# ProDocument_Schematic1_1_2023-10-08.net
KiCad netlist of a schematic drawn in EasyEDA Pro
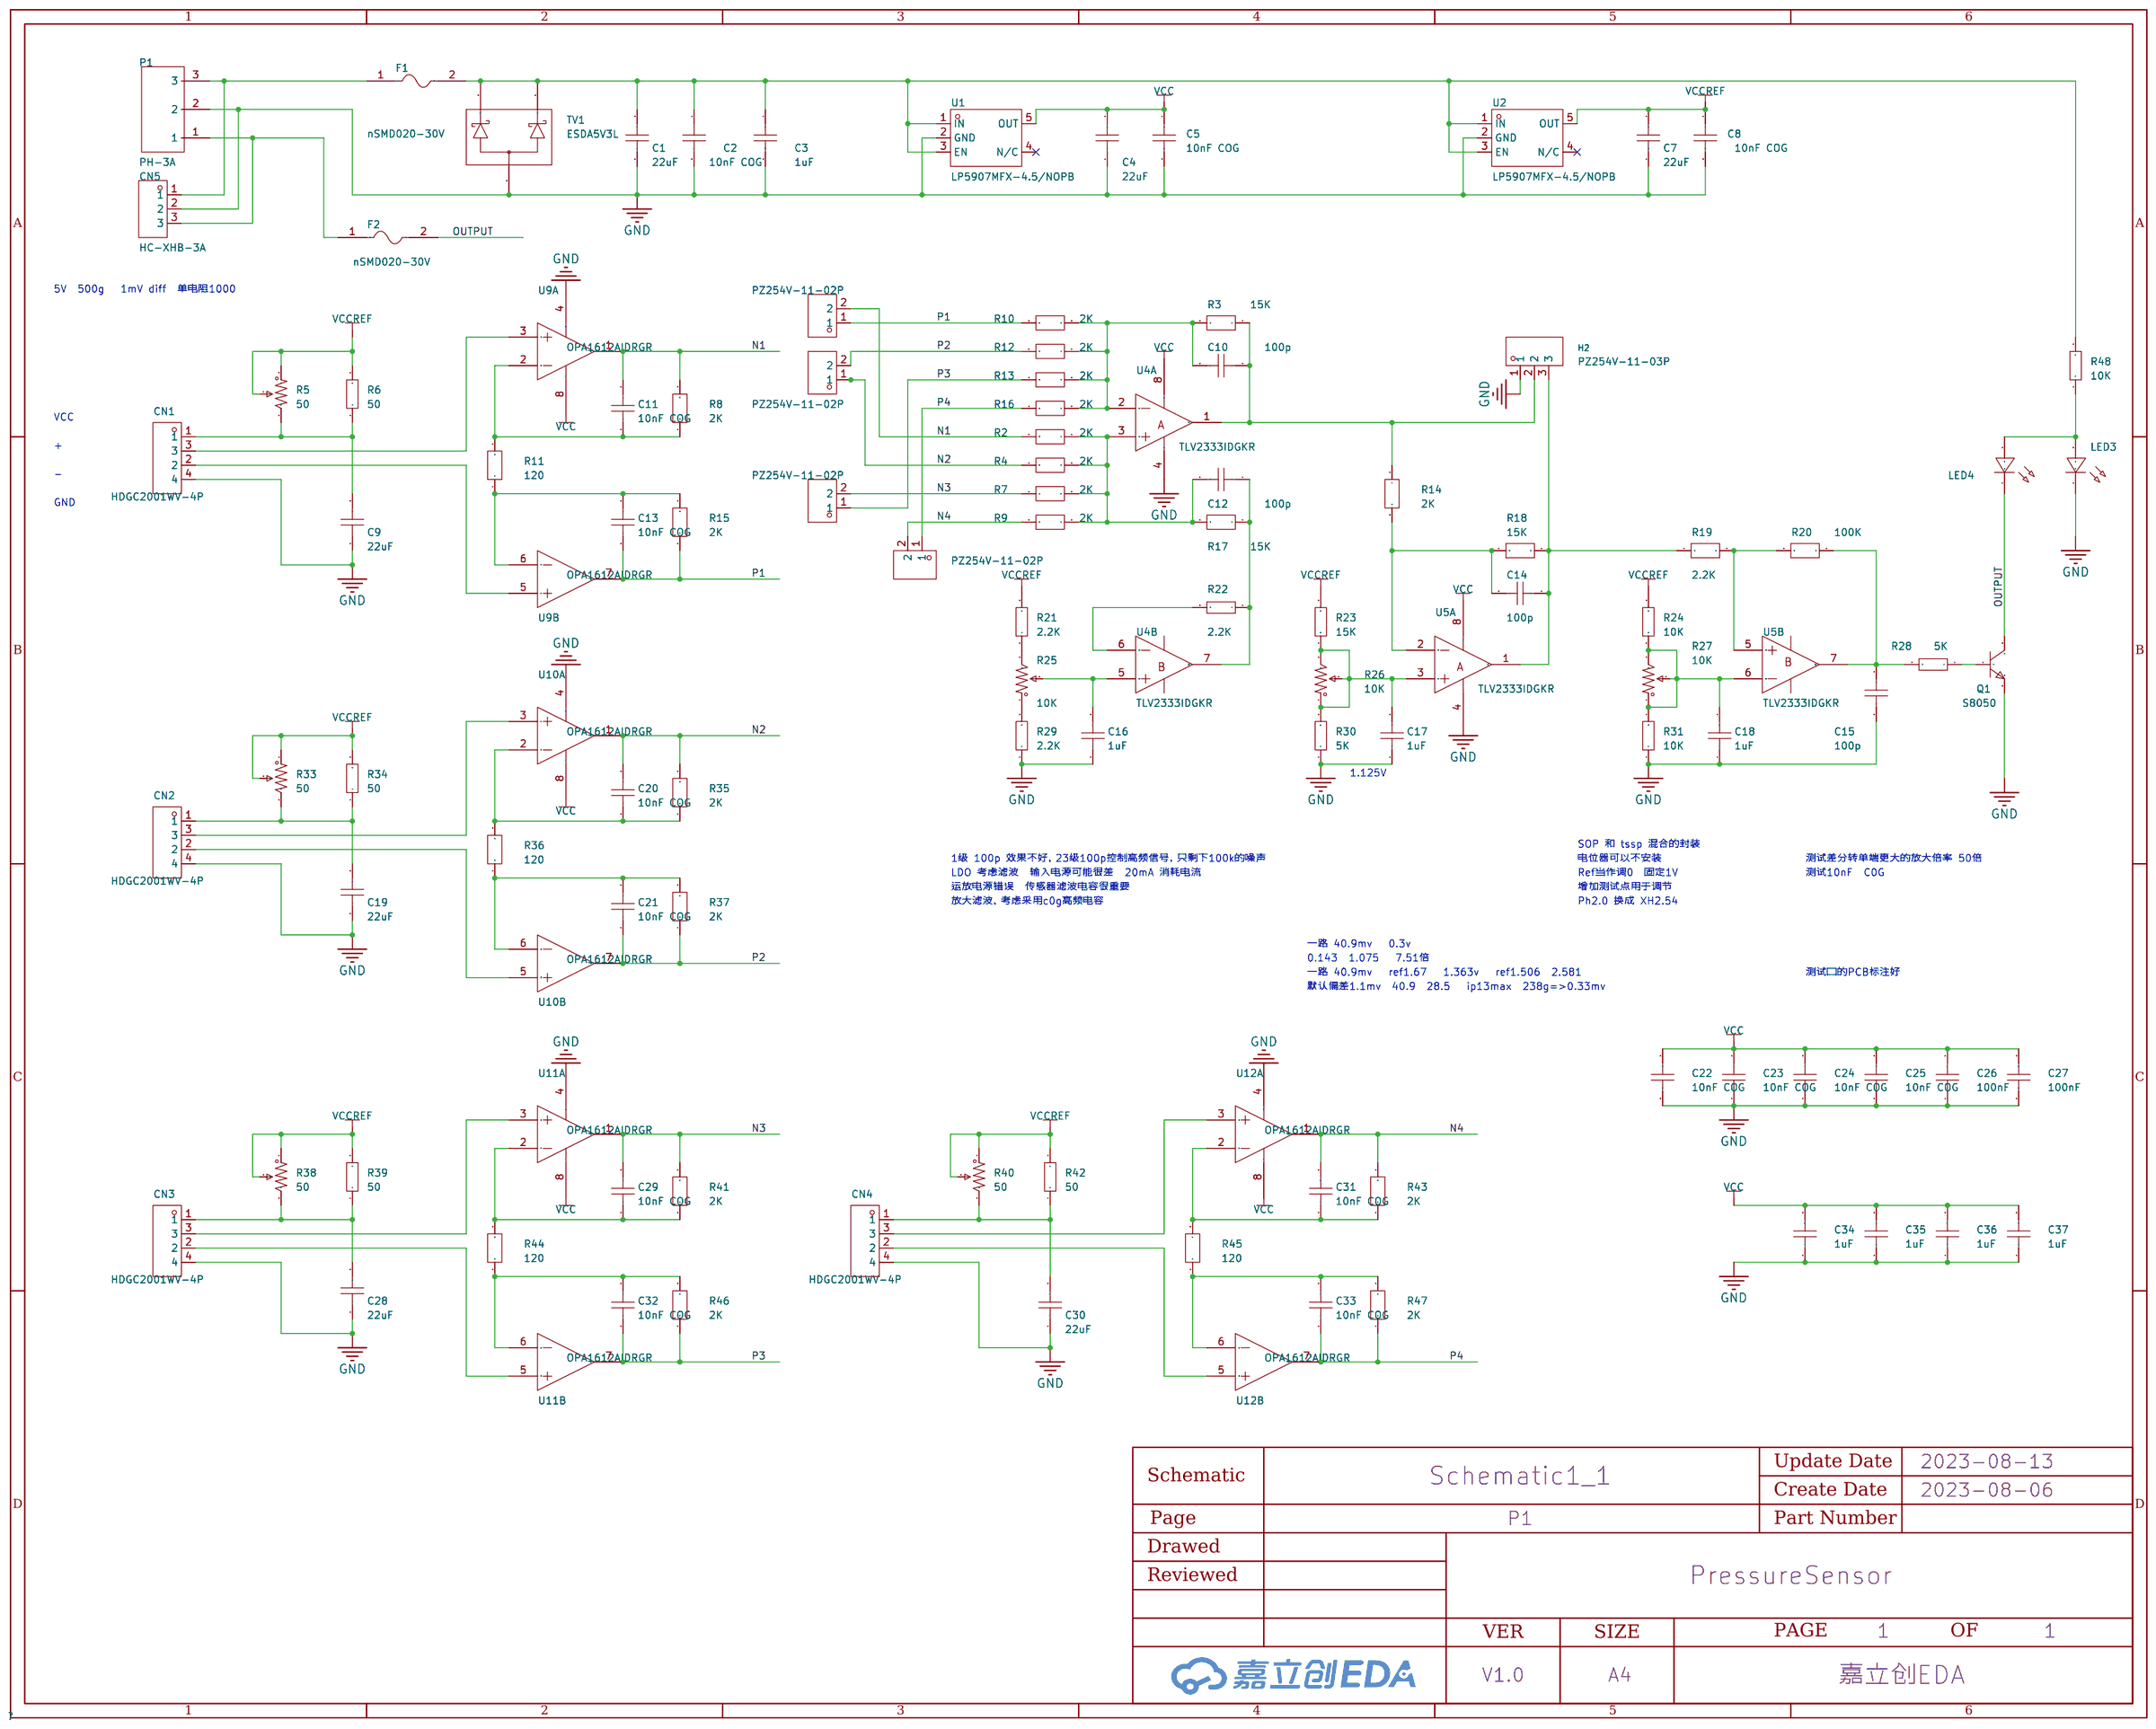
[diagram p0: schematic sheet]

(export (version "E")
  (design (tool "Eeschema 10.0.6"))
  (components
    (comp (ref "C1")
      (value "22uF")
      (footprint "easyedapro:R0402")
      (libsource (lib "easyedapro") (part "CapAcitance"))
    )
    (comp (ref "C2")
      (value "10nF COG")
      (footprint "easyedapro:R0402")
      (libsource (lib "easyedapro") (part "CapAcitance"))
    )
    (comp (ref "C3")
      (value "1uF")
      (footprint "easyedapro:R0402")
      (libsource (lib "easyedapro") (part "CapAcitance"))
    )
    (comp (ref "C4")
      (value "22uF")
      (footprint "easyedapro:R0402")
      (libsource (lib "easyedapro") (part "CapAcitance"))
    )
    (comp (ref "C5")
      (value "10nF COG")
      (footprint "easyedapro:R0402")
      (libsource (lib "easyedapro") (part "CapAcitance"))
    )
    (comp (ref "C7")
      (value "22uF")
      (footprint "easyedapro:R0402")
      (libsource (lib "easyedapro") (part "CapAcitance"))
    )
    (comp (ref "C8")
      (value "10nF COG")
      (footprint "easyedapro:R0402")
      (libsource (lib "easyedapro") (part "CapAcitance"))
    )
    (comp (ref "C9")
      (value "22uF")
      (footprint "easyedapro:R0402")
      (libsource (lib "easyedapro") (part "CapAcitance"))
    )
    (comp (ref "C10")
      (value "100p")
      (footprint "easyedapro:R0402")
      (libsource (lib "easyedapro") (part "CapAcitance"))
    )
    (comp (ref "C11")
      (value "10nF COG")
      (footprint "easyedapro:R0402")
      (libsource (lib "easyedapro") (part "CapAcitance"))
    )
    (comp (ref "C12")
      (value "100p")
      (footprint "easyedapro:R0402")
      (libsource (lib "easyedapro") (part "CapAcitance"))
    )
    (comp (ref "C13")
      (value "10nF COG")
      (footprint "easyedapro:R0402")
      (libsource (lib "easyedapro") (part "CapAcitance"))
    )
    (comp (ref "C14")
      (value "100p")
      (footprint "easyedapro:R0402")
      (libsource (lib "easyedapro") (part "CapAcitance"))
    )
    (comp (ref "C15")
      (value "100p")
      (footprint "easyedapro:R0402")
      (libsource (lib "easyedapro") (part "CapAcitance"))
    )
    (comp (ref "C16")
      (value "1uF")
      (footprint "easyedapro:R0402")
      (libsource (lib "easyedapro") (part "CapAcitance"))
    )
    (comp (ref "C17")
      (value "1uF")
      (footprint "easyedapro:R0402")
      (libsource (lib "easyedapro") (part "CapAcitance"))
    )
    (comp (ref "C18")
      (value "1uF")
      (footprint "easyedapro:R0402")
      (libsource (lib "easyedapro") (part "CapAcitance"))
    )
    (comp (ref "C19")
      (value "22uF")
      (footprint "easyedapro:R0402")
      (libsource (lib "easyedapro") (part "CapAcitance"))
    )
    (comp (ref "C20")
      (value "10nF COG")
      (footprint "easyedapro:R0402")
      (libsource (lib "easyedapro") (part "CapAcitance"))
    )
    (comp (ref "C21")
      (value "10nF COG")
      (footprint "easyedapro:R0402")
      (libsource (lib "easyedapro") (part "CapAcitance"))
    )
    (comp (ref "C22")
      (value "10nF COG")
      (footprint "easyedapro:R0402")
      (libsource (lib "easyedapro") (part "CapAcitance"))
    )
    (comp (ref "C23")
      (value "10nF COG")
      (footprint "easyedapro:R0402")
      (libsource (lib "easyedapro") (part "CapAcitance"))
    )
    (comp (ref "C24")
      (value "10nF COG")
      (footprint "easyedapro:R0402")
      (libsource (lib "easyedapro") (part "CapAcitance"))
    )
    (comp (ref "C25")
      (value "10nF COG")
      (footprint "easyedapro:R0402")
      (libsource (lib "easyedapro") (part "CapAcitance"))
    )
    (comp (ref "C26")
      (value "100nF")
      (footprint "easyedapro:R0402")
      (libsource (lib "easyedapro") (part "CapAcitance"))
    )
    (comp (ref "C27")
      (value "100nF")
      (footprint "easyedapro:R0402")
      (libsource (lib "easyedapro") (part "CapAcitance"))
    )
    (comp (ref "C28")
      (value "22uF")
      (footprint "easyedapro:R0402")
      (libsource (lib "easyedapro") (part "CapAcitance"))
    )
    (comp (ref "C29")
      (value "10nF COG")
      (footprint "easyedapro:R0402")
      (libsource (lib "easyedapro") (part "CapAcitance"))
    )
    (comp (ref "C30")
      (value "22uF")
      (footprint "easyedapro:R0402")
      (libsource (lib "easyedapro") (part "CapAcitance"))
    )
    (comp (ref "C31")
      (value "10nF COG")
      (footprint "easyedapro:R0402")
      (libsource (lib "easyedapro") (part "CapAcitance"))
    )
    (comp (ref "C32")
      (value "10nF COG")
      (footprint "easyedapro:R0402")
      (libsource (lib "easyedapro") (part "CapAcitance"))
    )
    (comp (ref "C33")
      (value "10nF COG")
      (footprint "easyedapro:R0402")
      (libsource (lib "easyedapro") (part "CapAcitance"))
    )
    (comp (ref "C34")
      (value "1uF")
      (footprint "easyedapro:R0402")
      (libsource (lib "easyedapro") (part "CapAcitance"))
    )
    (comp (ref "C35")
      (value "1uF")
      (footprint "easyedapro:R0402")
      (libsource (lib "easyedapro") (part "CapAcitance"))
    )
    (comp (ref "C36")
      (value "1uF")
      (footprint "easyedapro:R0402")
      (libsource (lib "easyedapro") (part "CapAcitance"))
    )
    (comp (ref "C37")
      (value "1uF")
      (footprint "easyedapro:R0402")
      (libsource (lib "easyedapro") (part "CapAcitance"))
    )
    (comp (ref "CN1")
      (value "HDGC2001WV-4P")
      (footprint "easyedapro:CONN-TH_4P-P2.00_HDGC_HDGC2001WV-4P")
      (fields (field (name "Manufacturer") "HDGC(华德共创)"))
      (libsource (lib "easyedapro") (part "HDGC2001WV-4P"))
    )
    (comp (ref "CN2")
      (value "HDGC2001WV-4P")
      (footprint "easyedapro:CONN-TH_4P-P2.00_HDGC_HDGC2001WV-4P")
      (fields (field (name "Manufacturer") "HDGC(华德共创)"))
      (libsource (lib "easyedapro") (part "HDGC2001WV-4P"))
    )
    (comp (ref "CN3")
      (value "HDGC2001WV-4P")
      (footprint "easyedapro:CONN-TH_4P-P2.00_HDGC_HDGC2001WV-4P")
      (fields (field (name "Manufacturer") "HDGC(华德共创)"))
      (libsource (lib "easyedapro") (part "HDGC2001WV-4P"))
    )
    (comp (ref "CN4")
      (value "HDGC2001WV-4P")
      (footprint "easyedapro:CONN-TH_4P-P2.00_HDGC_HDGC2001WV-4P")
      (fields (field (name "Manufacturer") "HDGC(华德共创)"))
      (libsource (lib "easyedapro") (part "HDGC2001WV-4P"))
    )
    (comp (ref "CN5")
      (value "HC-XHB-3A")
      (footprint "easyedapro:CONN-TH_3P-P2.50_HC-XHB-3A")
      (description "参考系列:-;间距:2.5mm;插针结构:1x3P;排数:1;每排PIN数:3;行距:-;公母:公型插针;安装方式:直插;额定电流:3A;工作温度范围:-25°C~+85°C;")
      (fields (field (name "Manufacturer") "HCTL(华灿天禄)"))
      (libsource (lib "easyedapro") (part "HC-XHB-3A"))
    )
    (comp (ref "F1")
      (value "nSMD020-30V")
      (footprint "easyedapro:F1206")
      (description "最大电压:30V;最大电流:100A;保持电流:200mA;跳闸电流:460mA;")
      (fields (field (name "Manufacturer") "台湾陆海"))
      (libsource (lib "easyedapro") (part "nSMD020-30V"))
    )
    (comp (ref "F2")
      (value "nSMD020-30V")
      (footprint "easyedapro:F1206")
      (description "最大电压:30V;最大电流:100A;保持电流:200mA;跳闸电流:460mA;")
      (fields (field (name "Manufacturer") "台湾陆海"))
      (libsource (lib "easyedapro") (part "nSMD020-30V"))
    )
    (comp (ref "H2")
      (value "PZ254V-11-03P")
      (footprint "easyedapro:HDR-TH_3P-P2.54-V-M")
      (fields (field (name "Manufacturer") "XFCN(兴飞)"))
      (libsource (lib "easyedapro") (part "PZ254V-11-03P_C2937625"))
    )
    (comp (ref "H5")
      (value "PZ254V-11-02P")
      (footprint "easyedapro:HDR-TH_2P-P2.54-V-M")
      (fields (field (name "Manufacturer") "XFCN(兴飞)"))
      (libsource (lib "easyedapro") (part "PZ254V-11-02P"))
    )
    (comp (ref "H6")
      (value "PZ254V-11-02P")
      (footprint "easyedapro:HDR-TH_2P-P2.54-V-M")
      (fields (field (name "Manufacturer") "XFCN(兴飞)"))
      (libsource (lib "easyedapro") (part "PZ254V-11-02P"))
    )
    (comp (ref "H7")
      (value "PZ254V-11-02P")
      (footprint "easyedapro:HDR-TH_2P-P2.54-V-M")
      (fields (field (name "Manufacturer") "XFCN(兴飞)"))
      (libsource (lib "easyedapro") (part "PZ254V-11-02P"))
    )
    (comp (ref "H8")
      (value "PZ254V-11-02P")
      (footprint "easyedapro:HDR-TH_2P-P2.54-V-M")
      (fields (field (name "Manufacturer") "XFCN(兴飞)"))
      (libsource (lib "easyedapro") (part "PZ254V-11-02P"))
    )
    (comp (ref "LED3")
      (value "~")
      (footprint "easyedapro:LED_0603")
      (libsource (lib "easyedapro") (part "LED_B"))
    )
    (comp (ref "LED4")
      (value "~")
      (footprint "easyedapro:LED_0603")
      (libsource (lib "easyedapro") (part "LED_B"))
    )
    (comp (ref "P1")
      (value "PH-3A")
      (footprint "easyedapro:CONN-TH_12P-P2.00-H-W4.8_PH-3A")
      (description "参考系列:PH;间距:2mm;插针结构:1x3P;排数:1;每排PIN数:3;行距:-;安装方式:-;触头材质:-;")
      (fields (field (name "Manufacturer") "BOOMELE(博穆精密)"))
      (libsource (lib "easyedapro") (part "PH-3A RHOS"))
    )
    (comp (ref "Q1")
      (value "S8050")
      (footprint "easyedapro:SOT-23-3_L2.9-W1.6-P1.90-LS2.8-BR")
      (description "晶体管类型:NPN;集射极击穿电压(Vceo):25V;集电极电流(Ic):500mA;功率(Pd):300mW;直流电流增益(hFE@Ic,Vce):120@50mA,1V;")
      (fields (field (name "Manufacturer") "CJ(江苏长电/长晶)"))
      (libsource (lib "easyedapro") (part "S8050_C105433"))
    )
    (comp (ref "R2")
      (value "2K")
      (footprint "easyedapro:R0402")
      (description "阻值:4.7Ω;精度:±0.1%;温度系数:±25ppm/°C;")
      (fields (field (name "Manufacturer Part") "ARG02BTC4R70") (field (name "Manufacturer") "Viking(光颉)"))
      (libsource (lib "easyedapro") (part "ARG02BTC4R70"))
    )
    (comp (ref "R3")
      (value "15K")
      (footprint "easyedapro:R0402")
      (description "阻值:4.7Ω;精度:±0.1%;温度系数:±25ppm/°C;")
      (fields (field (name "Manufacturer Part") "ARG02BTC4R70") (field (name "Manufacturer") "Viking(光颉)"))
      (libsource (lib "easyedapro") (part "ARG02BTC4R70"))
    )
    (comp (ref "R4")
      (value "2K")
      (footprint "easyedapro:R0402")
      (description "阻值:4.7Ω;精度:±0.1%;温度系数:±25ppm/°C;")
      (fields (field (name "Manufacturer Part") "ARG02BTC4R70") (field (name "Manufacturer") "Viking(光颉)"))
      (libsource (lib "easyedapro") (part "ARG02BTC4R70"))
    )
    (comp (ref "R5")
      (value "50")
      (footprint "easyedapro:RES-ADJ-TH_3P-L10.0-W10.0-P2.50-L")
      (description "阻值:10kΩ;精度:±10%;")
      (fields (field (name "Manufacturer Part") "3296W-1-103") (field (name "Manufacturer") "BOCHEN(博晨)"))
      (libsource (lib "easyedapro") (part "3296W-1-103"))
    )
    (comp (ref "R6") (value "50") (footprint "easyedapro:R0402") (libsource (lib "easyedapro") (part "电阻")))
    (comp (ref "R7")
      (value "2K")
      (footprint "easyedapro:R0402")
      (description "阻值:4.7Ω;精度:±0.1%;温度系数:±25ppm/°C;")
      (fields (field (name "Manufacturer Part") "ARG02BTC4R70") (field (name "Manufacturer") "Viking(光颉)"))
      (libsource (lib "easyedapro") (part "ARG02BTC4R70"))
    )
    (comp (ref "R8")
      (value "2K")
      (footprint "easyedapro:R0402")
      (description "阻值:4.7Ω;精度:±0.1%;温度系数:±25ppm/°C;")
      (fields (field (name "Manufacturer Part") "ARG02BTC4R70") (field (name "Manufacturer") "Viking(光颉)"))
      (libsource (lib "easyedapro") (part "ARG02BTC4R70"))
    )
    (comp (ref "R9")
      (value "2K")
      (footprint "easyedapro:R0402")
      (description "阻值:4.7Ω;精度:±0.1%;温度系数:±25ppm/°C;")
      (fields (field (name "Manufacturer Part") "ARG02BTC4R70") (field (name "Manufacturer") "Viking(光颉)"))
      (libsource (lib "easyedapro") (part "ARG02BTC4R70"))
    )
    (comp (ref "R10")
      (value "2K")
      (footprint "easyedapro:R0402")
      (description "阻值:4.7Ω;精度:±0.1%;温度系数:±25ppm/°C;")
      (fields (field (name "Manufacturer Part") "ARG02BTC4R70") (field (name "Manufacturer") "Viking(光颉)"))
      (libsource (lib "easyedapro") (part "ARG02BTC4R70"))
    )
    (comp (ref "R11")
      (value "120")
      (footprint "easyedapro:R0402")
      (description "阻值:4.7Ω;精度:±0.1%;温度系数:±25ppm/°C;")
      (fields (field (name "Manufacturer Part") "ARG02BTC4R70") (field (name "Manufacturer") "Viking(光颉)"))
      (libsource (lib "easyedapro") (part "ARG02BTC4R70"))
    )
    (comp (ref "R12")
      (value "2K")
      (footprint "easyedapro:R0402")
      (description "阻值:4.7Ω;精度:±0.1%;温度系数:±25ppm/°C;")
      (fields (field (name "Manufacturer Part") "ARG02BTC4R70") (field (name "Manufacturer") "Viking(光颉)"))
      (libsource (lib "easyedapro") (part "ARG02BTC4R70"))
    )
    (comp (ref "R13")
      (value "2K")
      (footprint "easyedapro:R0402")
      (description "阻值:4.7Ω;精度:±0.1%;温度系数:±25ppm/°C;")
      (fields (field (name "Manufacturer Part") "ARG02BTC4R70") (field (name "Manufacturer") "Viking(光颉)"))
      (libsource (lib "easyedapro") (part "ARG02BTC4R70"))
    )
    (comp (ref "R14")
      (value "2K")
      (footprint "easyedapro:R0402")
      (description "阻值:4.7Ω;精度:±0.1%;温度系数:±25ppm/°C;")
      (fields (field (name "Manufacturer Part") "ARG02BTC4R70") (field (name "Manufacturer") "Viking(光颉)"))
      (libsource (lib "easyedapro") (part "ARG02BTC4R70"))
    )
    (comp (ref "R15")
      (value "2K")
      (footprint "easyedapro:R0402")
      (description "阻值:4.7Ω;精度:±0.1%;温度系数:±25ppm/°C;")
      (fields (field (name "Manufacturer Part") "ARG02BTC4R70") (field (name "Manufacturer") "Viking(光颉)"))
      (libsource (lib "easyedapro") (part "ARG02BTC4R70"))
    )
    (comp (ref "R16")
      (value "2K")
      (footprint "easyedapro:R0402")
      (description "阻值:4.7Ω;精度:±0.1%;温度系数:±25ppm/°C;")
      (fields (field (name "Manufacturer Part") "ARG02BTC4R70") (field (name "Manufacturer") "Viking(光颉)"))
      (libsource (lib "easyedapro") (part "ARG02BTC4R70"))
    )
    (comp (ref "R17")
      (value "15K")
      (footprint "easyedapro:R0402")
      (description "阻值:4.7Ω;精度:±0.1%;温度系数:±25ppm/°C;")
      (fields (field (name "Manufacturer Part") "ARG02BTC4R70") (field (name "Manufacturer") "Viking(光颉)"))
      (libsource (lib "easyedapro") (part "ARG02BTC4R70"))
    )
    (comp (ref "R18")
      (value "15K")
      (footprint "easyedapro:R0402")
      (description "阻值:4.7Ω;精度:±0.1%;温度系数:±25ppm/°C;")
      (fields (field (name "Manufacturer Part") "ARG02BTC4R70") (field (name "Manufacturer") "Viking(光颉)"))
      (libsource (lib "easyedapro") (part "ARG02BTC4R70"))
    )
    (comp (ref "R19")
      (value "2.2K")
      (footprint "easyedapro:R0402")
      (description "阻值:4.7Ω;精度:±0.1%;温度系数:±25ppm/°C;")
      (fields (field (name "Manufacturer Part") "ARG02BTC4R70") (field (name "Manufacturer") "Viking(光颉)"))
      (libsource (lib "easyedapro") (part "ARG02BTC4R70"))
    )
    (comp (ref "R20")
      (value "100K")
      (footprint "easyedapro:R0402")
      (description "阻值:4.7Ω;精度:±0.1%;温度系数:±25ppm/°C;")
      (fields (field (name "Manufacturer Part") "ARG02BTC4R70") (field (name "Manufacturer") "Viking(光颉)"))
      (libsource (lib "easyedapro") (part "ARG02BTC4R70"))
    )
    (comp (ref "R21")
      (value "2.2K")
      (footprint "easyedapro:R0402")
      (libsource (lib "easyedapro") (part "电阻"))
    )
    (comp (ref "R22")
      (value "2.2K")
      (footprint "easyedapro:R0402")
      (libsource (lib "easyedapro") (part "电阻"))
    )
    (comp (ref "R23") (value "15K") (footprint "easyedapro:R0402") (libsource (lib "easyedapro") (part "电阻")))
    (comp (ref "R24") (value "10K") (footprint "easyedapro:R0402") (libsource (lib "easyedapro") (part "电阻")))
    (comp (ref "R25")
      (value "10K")
      (footprint "easyedapro:RES-ADJ-TH_3P-L10.0-W10.0-P2.50-L")
      (description "阻值:10kΩ;精度:±10%;")
      (fields (field (name "Manufacturer Part") "3296W-1-103") (field (name "Manufacturer") "BOCHEN(博晨)"))
      (libsource (lib "easyedapro") (part "3296W-1-103"))
    )
    (comp (ref "R26")
      (value "10K")
      (footprint "easyedapro:RES-ADJ-TH_3P-L10.0-W10.0-P2.50-L")
      (description "阻值:10kΩ;精度:±10%;")
      (fields (field (name "Manufacturer Part") "3296W-1-103") (field (name "Manufacturer") "BOCHEN(博晨)"))
      (libsource (lib "easyedapro") (part "3296W-1-103"))
    )
    (comp (ref "R27")
      (value "10K")
      (footprint "easyedapro:RES-ADJ-TH_3P-L10.0-W10.0-P2.50-L")
      (description "阻值:10kΩ;精度:±10%;")
      (fields (field (name "Manufacturer Part") "3296W-1-103") (field (name "Manufacturer") "BOCHEN(博晨)"))
      (libsource (lib "easyedapro") (part "3296W-1-103"))
    )
    (comp (ref "R28") (value "5K") (footprint "easyedapro:R0402") (libsource (lib "easyedapro") (part "电阻")))
    (comp (ref "R29")
      (value "2.2K")
      (footprint "easyedapro:R0402")
      (libsource (lib "easyedapro") (part "电阻"))
    )
    (comp (ref "R30") (value "5K") (footprint "easyedapro:R0402") (libsource (lib "easyedapro") (part "电阻")))
    (comp (ref "R31") (value "10K") (footprint "easyedapro:R0402") (libsource (lib "easyedapro") (part "电阻")))
    (comp (ref "R33")
      (value "50")
      (footprint "easyedapro:RES-ADJ-TH_3P-L10.0-W10.0-P2.50-L")
      (description "阻值:10kΩ;精度:±10%;")
      (fields (field (name "Manufacturer Part") "3296W-1-103") (field (name "Manufacturer") "BOCHEN(博晨)"))
      (libsource (lib "easyedapro") (part "3296W-1-103"))
    )
    (comp (ref "R34") (value "50") (footprint "easyedapro:R0402") (libsource (lib "easyedapro") (part "电阻")))
    (comp (ref "R35")
      (value "2K")
      (footprint "easyedapro:R0402")
      (description "阻值:4.7Ω;精度:±0.1%;温度系数:±25ppm/°C;")
      (fields (field (name "Manufacturer Part") "ARG02BTC4R70") (field (name "Manufacturer") "Viking(光颉)"))
      (libsource (lib "easyedapro") (part "ARG02BTC4R70"))
    )
    (comp (ref "R36")
      (value "120")
      (footprint "easyedapro:R0402")
      (description "阻值:4.7Ω;精度:±0.1%;温度系数:±25ppm/°C;")
      (fields (field (name "Manufacturer Part") "ARG02BTC4R70") (field (name "Manufacturer") "Viking(光颉)"))
      (libsource (lib "easyedapro") (part "ARG02BTC4R70"))
    )
    (comp (ref "R37")
      (value "2K")
      (footprint "easyedapro:R0402")
      (description "阻值:4.7Ω;精度:±0.1%;温度系数:±25ppm/°C;")
      (fields (field (name "Manufacturer Part") "ARG02BTC4R70") (field (name "Manufacturer") "Viking(光颉)"))
      (libsource (lib "easyedapro") (part "ARG02BTC4R70"))
    )
    (comp (ref "R38")
      (value "50")
      (footprint "easyedapro:RES-ADJ-TH_3P-L10.0-W10.0-P2.50-L")
      (description "阻值:10kΩ;精度:±10%;")
      (fields (field (name "Manufacturer Part") "3296W-1-103") (field (name "Manufacturer") "BOCHEN(博晨)"))
      (libsource (lib "easyedapro") (part "3296W-1-103"))
    )
    (comp (ref "R39") (value "50") (footprint "easyedapro:R0402") (libsource (lib "easyedapro") (part "电阻")))
    (comp (ref "R40")
      (value "50")
      (footprint "easyedapro:RES-ADJ-TH_3P-L10.0-W10.0-P2.50-L")
      (description "阻值:10kΩ;精度:±10%;")
      (fields (field (name "Manufacturer Part") "3296W-1-103") (field (name "Manufacturer") "BOCHEN(博晨)"))
      (libsource (lib "easyedapro") (part "3296W-1-103"))
    )
    (comp (ref "R41")
      (value "2K")
      (footprint "easyedapro:R0402")
      (description "阻值:4.7Ω;精度:±0.1%;温度系数:±25ppm/°C;")
      (fields (field (name "Manufacturer Part") "ARG02BTC4R70") (field (name "Manufacturer") "Viking(光颉)"))
      (libsource (lib "easyedapro") (part "ARG02BTC4R70"))
    )
    (comp (ref "R42") (value "50") (footprint "easyedapro:R0402") (libsource (lib "easyedapro") (part "电阻")))
    (comp (ref "R43")
      (value "2K")
      (footprint "easyedapro:R0402")
      (description "阻值:4.7Ω;精度:±0.1%;温度系数:±25ppm/°C;")
      (fields (field (name "Manufacturer Part") "ARG02BTC4R70") (field (name "Manufacturer") "Viking(光颉)"))
      (libsource (lib "easyedapro") (part "ARG02BTC4R70"))
    )
    (comp (ref "R44")
      (value "120")
      (footprint "easyedapro:R0402")
      (description "阻值:4.7Ω;精度:±0.1%;温度系数:±25ppm/°C;")
      (fields (field (name "Manufacturer Part") "ARG02BTC4R70") (field (name "Manufacturer") "Viking(光颉)"))
      (libsource (lib "easyedapro") (part "ARG02BTC4R70"))
    )
    (comp (ref "R45")
      (value "120")
      (footprint "easyedapro:R0402")
      (description "阻值:4.7Ω;精度:±0.1%;温度系数:±25ppm/°C;")
      (fields (field (name "Manufacturer Part") "ARG02BTC4R70") (field (name "Manufacturer") "Viking(光颉)"))
      (libsource (lib "easyedapro") (part "ARG02BTC4R70"))
    )
    (comp (ref "R46")
      (value "2K")
      (footprint "easyedapro:R0402")
      (description "阻值:4.7Ω;精度:±0.1%;温度系数:±25ppm/°C;")
      (fields (field (name "Manufacturer Part") "ARG02BTC4R70") (field (name "Manufacturer") "Viking(光颉)"))
      (libsource (lib "easyedapro") (part "ARG02BTC4R70"))
    )
    (comp (ref "R47")
      (value "2K")
      (footprint "easyedapro:R0402")
      (description "阻值:4.7Ω;精度:±0.1%;温度系数:±25ppm/°C;")
      (fields (field (name "Manufacturer Part") "ARG02BTC4R70") (field (name "Manufacturer") "Viking(光颉)"))
      (libsource (lib "easyedapro") (part "ARG02BTC4R70"))
    )
    (comp (ref "R48") (value "10K") (footprint "easyedapro:R0402") (libsource (lib "easyedapro") (part "电阻")))
    (comp (ref "TV1")
      (value "ESDA5V3L")
      (footprint "easyedapro:SOT-23-3_L2.9-W1.6-P1.90-LS2.8-BR")
      (fields (field (name "Manufacturer") "ST(意法半导体)"))
      (libsource (lib "easyedapro") (part "ESDA5V3L"))
    )
    (comp (ref "U1")
      (value "LP5907MFX-4.5/NOPB")
      (footprint "easyedapro:TSOT-23-5_L2.9-W1.6-P0.95-LS2.8-BR")
      (description "输出类型:-;")
      (fields (field (name "Manufacturer") "TI(德州仪器)"))
      (libsource (lib "easyedapro") (part "LP5907MFX-4.5/NOPB"))
    )
    (comp (ref "U2")
      (value "LP5907MFX-4.5/NOPB")
      (footprint "easyedapro:TSOT-23-5_L2.9-W1.6-P0.95-LS2.8-BR")
      (description "输出类型:-;")
      (fields (field (name "Manufacturer") "TI(德州仪器)"))
      (libsource (lib "easyedapro") (part "LP5907MFX-4.5/NOPB"))
    )
    (comp (ref "U4")
      (value "TLV2333IDGKR")
      (footprint "easyedapro:VSSOP-8_L3.0-W3.0-P0.65-LS5.0-BL")
      (description "放大器组数:-;")
      (fields (field (name "Manufacturer") "TI(德州仪器)"))
      (libsource (lib "easyedapro") (part "TLV2333IDGKR"))
    )
    (comp (ref "U5")
      (value "TLV2333IDGKR")
      (footprint "easyedapro:VSSOP-8_L3.0-W3.0-P0.65-LS5.0-BL")
      (description "放大器组数:-;")
      (fields (field (name "Manufacturer") "TI(德州仪器)"))
      (libsource (lib "easyedapro") (part "TLV2333IDGKR"))
    )
    (comp (ref "U9")
      (value "OPA1612AIDRGR")
      (footprint "easyedapro:SON-8_L3.0-W3.0-P0.50-TL-EP_OPA1612AIDRGR")
      (description "具有 1.1nV/√Hz 噪声和较低 THD 的高精度 SoundPlus 音频运算放大器 8-SON -40 to 85")
      (fields (field (name "Manufacturer") "TI(德州仪器)"))
      (libsource (lib "easyedapro") (part "OPA1612AIDRGR"))
    )
    (comp (ref "U10")
      (value "OPA1612AIDRGR")
      (footprint "easyedapro:SON-8_L3.0-W3.0-P0.50-TL-EP_OPA1612AIDRGR")
      (description "具有 1.1nV/√Hz 噪声和较低 THD 的高精度 SoundPlus 音频运算放大器 8-SON -40 to 85")
      (fields (field (name "Manufacturer") "TI(德州仪器)"))
      (libsource (lib "easyedapro") (part "OPA1612AIDRGR"))
    )
    (comp (ref "U11")
      (value "OPA1612AIDRGR")
      (footprint "easyedapro:SON-8_L3.0-W3.0-P0.50-TL-EP_OPA1612AIDRGR")
      (description "具有 1.1nV/√Hz 噪声和较低 THD 的高精度 SoundPlus 音频运算放大器 8-SON -40 to 85")
      (fields (field (name "Manufacturer") "TI(德州仪器)"))
      (libsource (lib "easyedapro") (part "OPA1612AIDRGR"))
    )
    (comp (ref "U12")
      (value "OPA1612AIDRGR")
      (footprint "easyedapro:SON-8_L3.0-W3.0-P0.50-TL-EP_OPA1612AIDRGR")
      (description "具有 1.1nV/√Hz 噪声和较低 THD 的高精度 SoundPlus 音频运算放大器 8-SON -40 to 85")
      (fields (field (name "Manufacturer") "TI(德州仪器)"))
      (libsource (lib "easyedapro") (part "OPA1612AIDRGR"))
    )
  )
  (nets
    (net (code "1") (name "/N1") (class "Default")
      (node (ref "C11") (pin "2") (pinfunction "2_2") (pintype "input"))
      (node (ref "H5") (pin "2") (pinfunction "2_2") (pintype "input"))
      (node (ref "R2") (pin "2") (pinfunction "2_2") (pintype "input"))
      (node (ref "R8") (pin "2") (pinfunction "2_2") (pintype "input"))
      (node (ref "U9") (pin "1") (pinfunction "OUTA_1") (pintype "output"))
    )
    (net (code "2") (name "/N2") (class "Default")
      (node (ref "C20") (pin "2") (pinfunction "2_2") (pintype "input"))
      (node (ref "H8") (pin "1") (pinfunction "1_1") (pintype "input"))
      (node (ref "R35") (pin "2") (pinfunction "2_2") (pintype "input"))
      (node (ref "R4") (pin "2") (pinfunction "2_2") (pintype "input"))
      (node (ref "U10") (pin "1") (pinfunction "OUTA_1") (pintype "output"))
    )
    (net (code "3") (name "/N3") (class "Default")
      (node (ref "C29") (pin "2") (pinfunction "2_2") (pintype "input"))
      (node (ref "H6") (pin "2") (pinfunction "2_2") (pintype "input"))
      (node (ref "R41") (pin "2") (pinfunction "2_2") (pintype "input"))
      (node (ref "R7") (pin "2") (pinfunction "2_2") (pintype "input"))
      (node (ref "U11") (pin "1") (pinfunction "OUTA_1") (pintype "output"))
    )
    (net (code "4") (name "/N4") (class "Default")
      (node (ref "C31") (pin "2") (pinfunction "2_2") (pintype "input"))
      (node (ref "H7") (pin "2") (pinfunction "2_2") (pintype "input"))
      (node (ref "R43") (pin "2") (pinfunction "2_2") (pintype "input"))
      (node (ref "R9") (pin "2") (pinfunction "2_2") (pintype "input"))
      (node (ref "U12") (pin "1") (pinfunction "OUTA_1") (pintype "output"))
    )
    (net (code "5") (name "/OUTPUT") (class "Default")
      (node (ref "F2") (pin "2") (pinfunction "2_2") (pintype "input"))
      (node (ref "LED4") (pin "1") (pinfunction "C_1") (pintype "input"))
      (node (ref "Q1") (pin "3") (pinfunction "3_3") (pintype "input"))
    )
    (net (code "6") (name "/P1") (class "Default")
      (node (ref "C13") (pin "1") (pinfunction "1_1") (pintype "input"))
      (node (ref "H5") (pin "1") (pinfunction "1_1") (pintype "input"))
      (node (ref "R10") (pin "2") (pinfunction "2_2") (pintype "input"))
      (node (ref "R15") (pin "1") (pinfunction "1_1") (pintype "input"))
      (node (ref "U9") (pin "7") (pinfunction "OUTB_7") (pintype "output"))
    )
    (net (code "7") (name "/P2") (class "Default")
      (node (ref "C21") (pin "1") (pinfunction "1_1") (pintype "input"))
      (node (ref "H8") (pin "2") (pinfunction "2_2") (pintype "input"))
      (node (ref "R12") (pin "2") (pinfunction "2_2") (pintype "input"))
      (node (ref "R37") (pin "1") (pinfunction "1_1") (pintype "input"))
      (node (ref "U10") (pin "7") (pinfunction "OUTB_7") (pintype "output"))
    )
    (net (code "8") (name "/P3") (class "Default")
      (node (ref "C32") (pin "1") (pinfunction "1_1") (pintype "input"))
      (node (ref "H6") (pin "1") (pinfunction "1_1") (pintype "input"))
      (node (ref "R13") (pin "2") (pinfunction "2_2") (pintype "input"))
      (node (ref "R46") (pin "1") (pinfunction "1_1") (pintype "input"))
      (node (ref "U11") (pin "7") (pinfunction "OUTB_7") (pintype "output"))
    )
    (net (code "9") (name "/P4") (class "Default")
      (node (ref "C33") (pin "1") (pinfunction "1_1") (pintype "input"))
      (node (ref "H7") (pin "1") (pinfunction "1_1") (pintype "input"))
      (node (ref "R16") (pin "2") (pinfunction "2_2") (pintype "input"))
      (node (ref "R47") (pin "1") (pinfunction "1_1") (pintype "input"))
      (node (ref "U12") (pin "7") (pinfunction "OUTB_7") (pintype "output"))
    )
    (net (code "10") (name "GND") (class "Default")
      (node (ref "C1") (pin "1") (pinfunction "1_1") (pintype "input"))
      (node (ref "C15") (pin "2") (pinfunction "2_2") (pintype "input"))
      (node (ref "C16") (pin "1") (pinfunction "1_1") (pintype "input"))
      (node (ref "C17") (pin "1") (pinfunction "1_1") (pintype "input"))
      (node (ref "C18") (pin "1") (pinfunction "1_1") (pintype "input"))
      (node (ref "C19") (pin "1") (pinfunction "1_1") (pintype "input"))
      (node (ref "C2") (pin "2") (pinfunction "2_2") (pintype "input"))
      (node (ref "C22") (pin "1") (pinfunction "1_1") (pintype "input"))
      (node (ref "C23") (pin "1") (pinfunction "1_1") (pintype "input"))
      (node (ref "C24") (pin "1") (pinfunction "1_1") (pintype "input"))
      (node (ref "C25") (pin "1") (pinfunction "1_1") (pintype "input"))
      (node (ref "C26") (pin "1") (pinfunction "1_1") (pintype "input"))
      (node (ref "C27") (pin "1") (pinfunction "1_1") (pintype "input"))
      (node (ref "C28") (pin "1") (pinfunction "1_1") (pintype "input"))
      (node (ref "C3") (pin "2") (pinfunction "2_2") (pintype "input"))
      (node (ref "C30") (pin "1") (pinfunction "1_1") (pintype "input"))
      (node (ref "C34") (pin "1") (pinfunction "1_1") (pintype "input"))
      (node (ref "C35") (pin "1") (pinfunction "1_1") (pintype "input"))
      (node (ref "C36") (pin "1") (pinfunction "1_1") (pintype "input"))
      (node (ref "C37") (pin "1") (pinfunction "1_1") (pintype "input"))
      (node (ref "C4") (pin "1") (pinfunction "1_1") (pintype "input"))
      (node (ref "C5") (pin "2") (pinfunction "2_2") (pintype "input"))
      (node (ref "C7") (pin "1") (pinfunction "1_1") (pintype "input"))
      (node (ref "C8") (pin "2") (pinfunction "2_2") (pintype "input"))
      (node (ref "C9") (pin "1") (pinfunction "1_1") (pintype "input"))
      (node (ref "CN1") (pin "4") (pinfunction "4_4") (pintype "input"))
      (node (ref "CN2") (pin "4") (pinfunction "4_4") (pintype "input"))
      (node (ref "CN3") (pin "4") (pinfunction "4_4") (pintype "input"))
      (node (ref "CN4") (pin "4") (pinfunction "4_4") (pintype "input"))
      (node (ref "CN5") (pin "2") (pinfunction "2_2") (pintype "input"))
      (node (ref "H2") (pin "1") (pinfunction "1_1") (pintype "input"))
      (node (ref "LED3") (pin "1") (pinfunction "C_1") (pintype "input"))
      (node (ref "P1") (pin "2") (pinfunction "2_2") (pintype "input"))
      (node (ref "Q1") (pin "2") (pinfunction "2_2") (pintype "input"))
      (node (ref "R29") (pin "1") (pinfunction "1_1") (pintype "input"))
      (node (ref "R30") (pin "1") (pinfunction "1_1") (pintype "input"))
      (node (ref "R31") (pin "1") (pinfunction "1_1") (pintype "input"))
      (node (ref "TV1") (pin "3") (pinfunction "3_3") (pintype "input"))
      (node (ref "U1") (pin "2") (pinfunction "GND_2") (pintype "input"))
      (node (ref "U10") (pin "4") (pinfunction "GND_4") (pintype "input"))
      (node (ref "U11") (pin "4") (pinfunction "GND_4") (pintype "input"))
      (node (ref "U12") (pin "4") (pinfunction "GND_4") (pintype "input"))
      (node (ref "U2") (pin "2") (pinfunction "GND_2") (pintype "input"))
      (node (ref "U4") (pin "4") (pinfunction "V-_4") (pintype "input"))
      (node (ref "U5") (pin "4") (pinfunction "V-_4") (pintype "input"))
      (node (ref "U9") (pin "4") (pinfunction "GND_4") (pintype "input"))
    )
    (net (code "11") (name "Net-(C9-Pad2)") (class "Default")
      (node (ref "C9") (pin "2") (pinfunction "2_2") (pintype "input"))
      (node (ref "CN1") (pin "1") (pinfunction "1_1") (pintype "input"))
      (node (ref "R5") (pin "3") (pinfunction "3_3") (pintype "input"))
      (node (ref "R6") (pin "1") (pinfunction "1_1") (pintype "input"))
    )
    (net (code "12") (name "Net-(C19-Pad2)") (class "Default")
      (node (ref "C19") (pin "2") (pinfunction "2_2") (pintype "input"))
      (node (ref "CN2") (pin "1") (pinfunction "1_1") (pintype "input"))
      (node (ref "R33") (pin "3") (pinfunction "3_3") (pintype "input"))
      (node (ref "R34") (pin "1") (pinfunction "1_1") (pintype "input"))
    )
    (net (code "13") (name "Net-(C28-Pad2)") (class "Default")
      (node (ref "C28") (pin "2") (pinfunction "2_2") (pintype "input"))
      (node (ref "CN3") (pin "1") (pinfunction "1_1") (pintype "input"))
      (node (ref "R38") (pin "3") (pinfunction "3_3") (pintype "input"))
      (node (ref "R39") (pin "1") (pinfunction "1_1") (pintype "input"))
    )
    (net (code "14") (name "Net-(C30-Pad2)") (class "Default")
      (node (ref "C30") (pin "2") (pinfunction "2_2") (pintype "input"))
      (node (ref "CN4") (pin "1") (pinfunction "1_1") (pintype "input"))
      (node (ref "R40") (pin "3") (pinfunction "3_3") (pintype "input"))
      (node (ref "R42") (pin "1") (pinfunction "1_1") (pintype "input"))
    )
    (net (code "15") (name "Net-(CN5-Pad1)") (class "Default")
      (node (ref "CN5") (pin "1") (pinfunction "1_1") (pintype "input"))
      (node (ref "F1") (pin "1") (pinfunction "1_1") (pintype "input"))
      (node (ref "P1") (pin "3") (pinfunction "3_3") (pintype "input"))
    )
    (net (code "16") (name "Net-(CN5-Pad3)") (class "Default")
      (node (ref "CN5") (pin "3") (pinfunction "3_3") (pintype "input"))
      (node (ref "F2") (pin "1") (pinfunction "1_1") (pintype "input"))
      (node (ref "P1") (pin "1") (pinfunction "1_1") (pintype "input"))
    )
    (net (code "17") (name "Net-(LED3-A)") (class "Default")
      (node (ref "LED3") (pin "2") (pinfunction "A_2") (pintype "input"))
      (node (ref "LED4") (pin "2") (pinfunction "A_2") (pintype "input"))
      (node (ref "R48") (pin "1") (pinfunction "1_1") (pintype "input"))
    )
    (net (code "18") (name "Net-(Q1-Pad1)") (class "Default")
      (node (ref "Q1") (pin "1") (pinfunction "1_1") (pintype "input"))
      (node (ref "R28") (pin "1") (pinfunction "1_1") (pintype "input"))
    )
    (net (code "19") (name "Net-(R21-Pad1)") (class "Default")
      (node (ref "R21") (pin "1") (pinfunction "1_1") (pintype "input"))
      (node (ref "R25") (pin "3") (pinfunction "3_3") (pintype "input"))
    )
    (net (code "20") (name "Net-(R25-Pad1)") (class "Default")
      (node (ref "R25") (pin "1") (pinfunction "1_1") (pintype "input"))
      (node (ref "R29") (pin "2") (pinfunction "2_2") (pintype "input"))
    )
    (net (code "21") (name "Net-(U1-EN)") (class "Default")
      (node (ref "C1") (pin "2") (pinfunction "2_2") (pintype "input"))
      (node (ref "C2") (pin "1") (pinfunction "1_1") (pintype "input"))
      (node (ref "C3") (pin "1") (pinfunction "1_1") (pintype "input"))
      (node (ref "F1") (pin "2") (pinfunction "2_2") (pintype "input"))
      (node (ref "R48") (pin "2") (pinfunction "2_2") (pintype "input"))
      (node (ref "TV1") (pin "1") (pinfunction "1_1") (pintype "input"))
      (node (ref "TV1") (pin "2") (pinfunction "2_2") (pintype "input"))
      (node (ref "U1") (pin "1") (pinfunction "IN_1") (pintype "input"))
      (node (ref "U1") (pin "3") (pinfunction "EN_3") (pintype "input"))
      (node (ref "U2") (pin "1") (pinfunction "IN_1") (pintype "input"))
      (node (ref "U2") (pin "3") (pinfunction "EN_3") (pintype "input"))
    )
    (net (code "22") (name "Net-(U4A-INA+)") (class "Default")
      (node (ref "C12") (pin "2") (pinfunction "2_2") (pintype "input"))
      (node (ref "R17") (pin "2") (pinfunction "2_2") (pintype "input"))
      (node (ref "R2") (pin "1") (pinfunction "1_1") (pintype "input"))
      (node (ref "R4") (pin "1") (pinfunction "1_1") (pintype "input"))
      (node (ref "R7") (pin "1") (pinfunction "1_1") (pintype "input"))
      (node (ref "R9") (pin "1") (pinfunction "1_1") (pintype "input"))
      (node (ref "U4") (pin "3") (pinfunction "INA+_3") (pintype "input"))
    )
    (net (code "23") (name "Net-(U4A-INA-)") (class "Default")
      (node (ref "C10") (pin "2") (pinfunction "2_2") (pintype "input"))
      (node (ref "R10") (pin "1") (pinfunction "1_1") (pintype "input"))
      (node (ref "R12") (pin "1") (pinfunction "1_1") (pintype "input"))
      (node (ref "R13") (pin "1") (pinfunction "1_1") (pintype "input"))
      (node (ref "R16") (pin "1") (pinfunction "1_1") (pintype "input"))
      (node (ref "R3") (pin "2") (pinfunction "2_2") (pintype "input"))
      (node (ref "U4") (pin "2") (pinfunction "INA-_2") (pintype "input"))
    )
    (net (code "24") (name "Net-(U4A-OUTA)") (class "Default")
      (node (ref "C10") (pin "1") (pinfunction "1_1") (pintype "input"))
      (node (ref "H2") (pin "2") (pinfunction "2_2") (pintype "input"))
      (node (ref "R14") (pin "1") (pinfunction "1_1") (pintype "input"))
      (node (ref "R3") (pin "1") (pinfunction "1_1") (pintype "input"))
      (node (ref "U4") (pin "1") (pinfunction "OUTA_1") (pintype "output"))
    )
    (net (code "25") (name "Net-(U4B-INB+)") (class "Default")
      (node (ref "C16") (pin "2") (pinfunction "2_2") (pintype "input"))
      (node (ref "R25") (pin "2") (pinfunction "2_2") (pintype "input"))
      (node (ref "U4") (pin "5") (pinfunction "INB+_5") (pintype "input"))
    )
    (net (code "26") (name "Net-(U4B-INB-)") (class "Default")
      (node (ref "R22") (pin "2") (pinfunction "2_2") (pintype "input"))
      (node (ref "U4") (pin "6") (pinfunction "INB-_6") (pintype "input"))
    )
    (net (code "27") (name "Net-(U4B-OUTB)") (class "Default")
      (node (ref "C12") (pin "1") (pinfunction "1_1") (pintype "input"))
      (node (ref "R17") (pin "1") (pinfunction "1_1") (pintype "input"))
      (node (ref "R22") (pin "1") (pinfunction "1_1") (pintype "input"))
      (node (ref "U4") (pin "7") (pinfunction "OUTB_7") (pintype "output"))
    )
    (net (code "28") (name "Net-(U5A-INA+)") (class "Default")
      (node (ref "C17") (pin "2") (pinfunction "2_2") (pintype "input"))
      (node (ref "R23") (pin "1") (pinfunction "1_1") (pintype "input"))
      (node (ref "R26") (pin "1") (pinfunction "1_1") (pintype "input"))
      (node (ref "R26") (pin "2") (pinfunction "2_2") (pintype "input"))
      (node (ref "R26") (pin "3") (pinfunction "3_3") (pintype "input"))
      (node (ref "R30") (pin "2") (pinfunction "2_2") (pintype "input"))
      (node (ref "U5") (pin "3") (pinfunction "INA+_3") (pintype "input"))
    )
    (net (code "29") (name "Net-(U5A-INA-)") (class "Default")
      (node (ref "C14") (pin "2") (pinfunction "2_2") (pintype "input"))
      (node (ref "R14") (pin "2") (pinfunction "2_2") (pintype "input"))
      (node (ref "R18") (pin "2") (pinfunction "2_2") (pintype "input"))
      (node (ref "U5") (pin "2") (pinfunction "INA-_2") (pintype "input"))
    )
    (net (code "30") (name "Net-(U5A-OUTA)") (class "Default")
      (node (ref "C14") (pin "1") (pinfunction "1_1") (pintype "input"))
      (node (ref "H2") (pin "3") (pinfunction "3_3") (pintype "input"))
      (node (ref "R18") (pin "1") (pinfunction "1_1") (pintype "input"))
      (node (ref "R19") (pin "1") (pinfunction "1_1") (pintype "input"))
      (node (ref "U5") (pin "1") (pinfunction "OUTA_1") (pintype "output"))
    )
    (net (code "31") (name "Net-(U5B-INB+)") (class "Default")
      (node (ref "R19") (pin "2") (pinfunction "2_2") (pintype "input"))
      (node (ref "R20") (pin "2") (pinfunction "2_2") (pintype "input"))
      (node (ref "U5") (pin "5") (pinfunction "INB+_5") (pintype "input"))
    )
    (net (code "32") (name "Net-(U5B-INB-)") (class "Default")
      (node (ref "C18") (pin "2") (pinfunction "2_2") (pintype "input"))
      (node (ref "R24") (pin "1") (pinfunction "1_1") (pintype "input"))
      (node (ref "R27") (pin "1") (pinfunction "1_1") (pintype "input"))
      (node (ref "R27") (pin "2") (pinfunction "2_2") (pintype "input"))
      (node (ref "R27") (pin "3") (pinfunction "3_3") (pintype "input"))
      (node (ref "R31") (pin "2") (pinfunction "2_2") (pintype "input"))
      (node (ref "U5") (pin "6") (pinfunction "INB-_6") (pintype "input"))
    )
    (net (code "33") (name "Net-(U5B-OUTB)") (class "Default")
      (node (ref "C15") (pin "1") (pinfunction "1_1") (pintype "input"))
      (node (ref "R20") (pin "1") (pinfunction "1_1") (pintype "input"))
      (node (ref "R28") (pin "2") (pinfunction "2_2") (pintype "input"))
      (node (ref "U5") (pin "7") (pinfunction "OUTB_7") (pintype "output"))
    )
    (net (code "34") (name "Net-(U9A-INA+)") (class "Default")
      (node (ref "CN1") (pin "3") (pinfunction "3_3") (pintype "input"))
      (node (ref "U9") (pin "3") (pinfunction "INA+_3") (pintype "input"))
    )
    (net (code "35") (name "Net-(U9A-INA-)") (class "Default")
      (node (ref "C11") (pin "1") (pinfunction "1_1") (pintype "input"))
      (node (ref "R11") (pin "2") (pinfunction "2_2") (pintype "input"))
      (node (ref "R8") (pin "1") (pinfunction "1_1") (pintype "input"))
      (node (ref "U9") (pin "2") (pinfunction "INA-_2") (pintype "input"))
    )
    (net (code "36") (name "Net-(U9B-INB+)") (class "Default")
      (node (ref "CN1") (pin "2") (pinfunction "2_2") (pintype "input"))
      (node (ref "U9") (pin "5") (pinfunction "INB+_5") (pintype "input"))
    )
    (net (code "37") (name "Net-(U9B-INB-)") (class "Default")
      (node (ref "C13") (pin "2") (pinfunction "2_2") (pintype "input"))
      (node (ref "R11") (pin "1") (pinfunction "1_1") (pintype "input"))
      (node (ref "R15") (pin "2") (pinfunction "2_2") (pintype "input"))
      (node (ref "U9") (pin "6") (pinfunction "INB-_6") (pintype "input"))
    )
    (net (code "38") (name "Net-(U10A-INA+)") (class "Default")
      (node (ref "CN2") (pin "3") (pinfunction "3_3") (pintype "input"))
      (node (ref "U10") (pin "3") (pinfunction "INA+_3") (pintype "input"))
    )
    (net (code "39") (name "Net-(U10A-INA-)") (class "Default")
      (node (ref "C20") (pin "1") (pinfunction "1_1") (pintype "input"))
      (node (ref "R35") (pin "1") (pinfunction "1_1") (pintype "input"))
      (node (ref "R36") (pin "2") (pinfunction "2_2") (pintype "input"))
      (node (ref "U10") (pin "2") (pinfunction "INA-_2") (pintype "input"))
    )
    (net (code "40") (name "Net-(U10B-INB+)") (class "Default")
      (node (ref "CN2") (pin "2") (pinfunction "2_2") (pintype "input"))
      (node (ref "U10") (pin "5") (pinfunction "INB+_5") (pintype "input"))
    )
    (net (code "41") (name "Net-(U10B-INB-)") (class "Default")
      (node (ref "C21") (pin "2") (pinfunction "2_2") (pintype "input"))
      (node (ref "R36") (pin "1") (pinfunction "1_1") (pintype "input"))
      (node (ref "R37") (pin "2") (pinfunction "2_2") (pintype "input"))
      (node (ref "U10") (pin "6") (pinfunction "INB-_6") (pintype "input"))
    )
    (net (code "42") (name "Net-(U11A-INA+)") (class "Default")
      (node (ref "CN3") (pin "3") (pinfunction "3_3") (pintype "input"))
      (node (ref "U11") (pin "3") (pinfunction "INA+_3") (pintype "input"))
    )
    (net (code "43") (name "Net-(U11A-INA-)") (class "Default")
      (node (ref "C29") (pin "1") (pinfunction "1_1") (pintype "input"))
      (node (ref "R41") (pin "1") (pinfunction "1_1") (pintype "input"))
      (node (ref "R44") (pin "2") (pinfunction "2_2") (pintype "input"))
      (node (ref "U11") (pin "2") (pinfunction "INA-_2") (pintype "input"))
    )
    (net (code "44") (name "Net-(U11B-INB+)") (class "Default")
      (node (ref "CN3") (pin "2") (pinfunction "2_2") (pintype "input"))
      (node (ref "U11") (pin "5") (pinfunction "INB+_5") (pintype "input"))
    )
    (net (code "45") (name "Net-(U11B-INB-)") (class "Default")
      (node (ref "C32") (pin "2") (pinfunction "2_2") (pintype "input"))
      (node (ref "R44") (pin "1") (pinfunction "1_1") (pintype "input"))
      (node (ref "R46") (pin "2") (pinfunction "2_2") (pintype "input"))
      (node (ref "U11") (pin "6") (pinfunction "INB-_6") (pintype "input"))
    )
    (net (code "46") (name "Net-(U12A-INA+)") (class "Default")
      (node (ref "CN4") (pin "3") (pinfunction "3_3") (pintype "input"))
      (node (ref "U12") (pin "3") (pinfunction "INA+_3") (pintype "input"))
    )
    (net (code "47") (name "Net-(U12A-INA-)") (class "Default")
      (node (ref "C31") (pin "1") (pinfunction "1_1") (pintype "input"))
      (node (ref "R43") (pin "1") (pinfunction "1_1") (pintype "input"))
      (node (ref "R45") (pin "2") (pinfunction "2_2") (pintype "input"))
      (node (ref "U12") (pin "2") (pinfunction "INA-_2") (pintype "input"))
    )
    (net (code "48") (name "Net-(U12B-INB+)") (class "Default")
      (node (ref "CN4") (pin "2") (pinfunction "2_2") (pintype "input"))
      (node (ref "U12") (pin "5") (pinfunction "INB+_5") (pintype "input"))
    )
    (net (code "49") (name "Net-(U12B-INB-)") (class "Default")
      (node (ref "C33") (pin "2") (pinfunction "2_2") (pintype "input"))
      (node (ref "R45") (pin "1") (pinfunction "1_1") (pintype "input"))
      (node (ref "R47") (pin "2") (pinfunction "2_2") (pintype "input"))
      (node (ref "U12") (pin "6") (pinfunction "INB-_6") (pintype "input"))
    )
    (net (code "50") (name "VCC") (class "Default")
      (node (ref "C22") (pin "2") (pinfunction "2_2") (pintype "input"))
      (node (ref "C23") (pin "2") (pinfunction "2_2") (pintype "input"))
      (node (ref "C24") (pin "2") (pinfunction "2_2") (pintype "input"))
      (node (ref "C25") (pin "2") (pinfunction "2_2") (pintype "input"))
      (node (ref "C26") (pin "2") (pinfunction "2_2") (pintype "input"))
      (node (ref "C27") (pin "2") (pinfunction "2_2") (pintype "input"))
      (node (ref "C34") (pin "2") (pinfunction "2_2") (pintype "input"))
      (node (ref "C35") (pin "2") (pinfunction "2_2") (pintype "input"))
      (node (ref "C36") (pin "2") (pinfunction "2_2") (pintype "input"))
      (node (ref "C37") (pin "2") (pinfunction "2_2") (pintype "input"))
      (node (ref "C4") (pin "2") (pinfunction "2_2") (pintype "input"))
      (node (ref "C5") (pin "1") (pinfunction "1_1") (pintype "input"))
      (node (ref "U1") (pin "5") (pinfunction "OUT_5") (pintype "input"))
      (node (ref "U10") (pin "8") (pinfunction "V+_8") (pintype "input"))
      (node (ref "U11") (pin "8") (pinfunction "V+_8") (pintype "input"))
      (node (ref "U12") (pin "8") (pinfunction "V+_8") (pintype "input"))
      (node (ref "U4") (pin "8") (pinfunction "V+_8") (pintype "input"))
      (node (ref "U5") (pin "8") (pinfunction "V+_8") (pintype "input"))
      (node (ref "U9") (pin "8") (pinfunction "V+_8") (pintype "input"))
    )
    (net (code "51") (name "VCCREF") (class "Default")
      (node (ref "C7") (pin "2") (pinfunction "2_2") (pintype "input"))
      (node (ref "C8") (pin "1") (pinfunction "1_1") (pintype "input"))
      (node (ref "R21") (pin "2") (pinfunction "2_2") (pintype "input"))
      (node (ref "R23") (pin "2") (pinfunction "2_2") (pintype "input"))
      (node (ref "R24") (pin "2") (pinfunction "2_2") (pintype "input"))
      (node (ref "R33") (pin "1") (pinfunction "1_1") (pintype "input"))
      (node (ref "R33") (pin "2") (pinfunction "2_2") (pintype "input"))
      (node (ref "R34") (pin "2") (pinfunction "2_2") (pintype "input"))
      (node (ref "R38") (pin "1") (pinfunction "1_1") (pintype "input"))
      (node (ref "R38") (pin "2") (pinfunction "2_2") (pintype "input"))
      (node (ref "R39") (pin "2") (pinfunction "2_2") (pintype "input"))
      (node (ref "R40") (pin "1") (pinfunction "1_1") (pintype "input"))
      (node (ref "R40") (pin "2") (pinfunction "2_2") (pintype "input"))
      (node (ref "R42") (pin "2") (pinfunction "2_2") (pintype "input"))
      (node (ref "R5") (pin "1") (pinfunction "1_1") (pintype "input"))
      (node (ref "R5") (pin "2") (pinfunction "2_2") (pintype "input"))
      (node (ref "R6") (pin "2") (pinfunction "2_2") (pintype "input"))
      (node (ref "U2") (pin "5") (pinfunction "OUT_5") (pintype "input"))
    )
    (net (code "52") (name "unconnected-(U1-N{slash}C-Pad4)") (class "Default")
      (node (ref "U1") (pin "4") (pinfunction "N/C_4") (pintype "input+no_connect"))
    )
    (net (code "53") (name "unconnected-(U2-N{slash}C-Pad4)") (class "Default")
      (node (ref "U2") (pin "4") (pinfunction "N/C_4") (pintype "input+no_connect"))
    )
  )
)
